# schematic.net
KiCad netlist of a schematic drawn in EAGLE
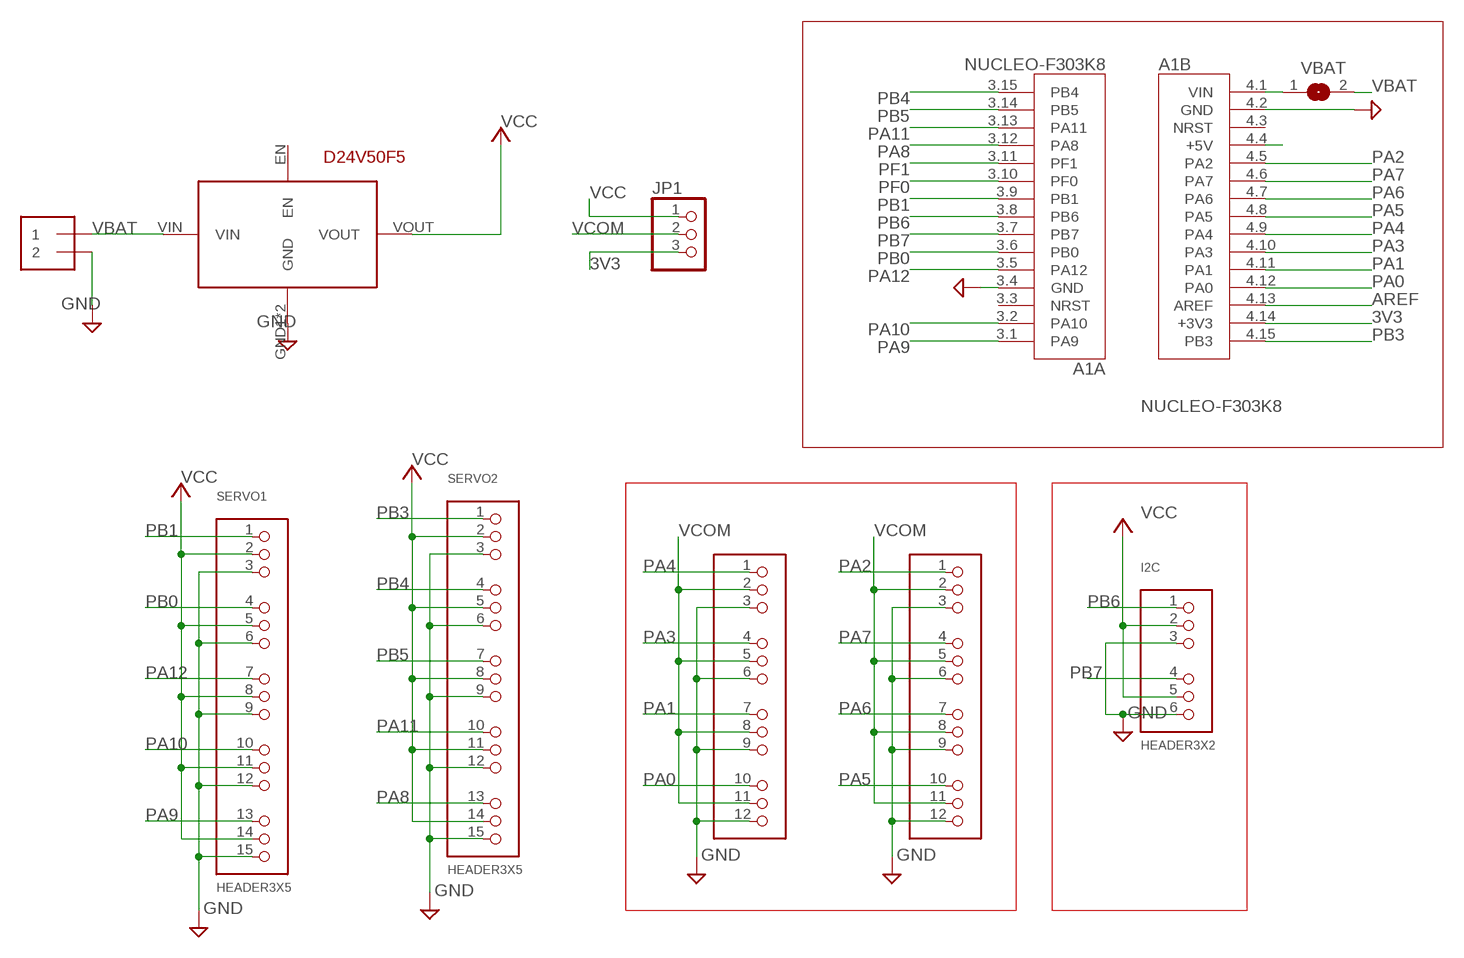
[diagram p0: schematic, sheet 1]

(export (version "E")
  (design (tool "Eeschema 10.0.6"))
  (components
    (comp (ref "A1")
      (value "NUCLEO-F303K8")
      (footprint "eagle-import:MODULE_NUCLEO-F303K8")
      (fields (field (name "MF") "STMicroelectronics"))
      (libsource (lib "eagle-import") (part "NUCLEO-F303K8"))
    )
    (comp (ref "ADC")
      (value "HEADER-3X04")
      (footprint "eagle-import:3X04")
      (fields (field (name "SPICEPREFIX") "X"))
      (libsource (lib "eagle-import") (part "HEADER-3X04"))
    )
    (comp (ref "ADC_DAC")
      (value "HEADER-3X04")
      (footprint "eagle-import:3X04")
      (libsource (lib "eagle-import") (part "HEADER-3X04"))
    )
    (comp (ref "I2C")
      (value "HEADER3X2")
      (footprint "eagle-import:HEADER3X2")
      (libsource (lib "eagle-import") (part "HEADER3X2"))
    )
    (comp (ref "J1")
      (value "1X2-3.5MM")
      (footprint "eagle-import:1X2-3.5MM")
      (libsource (lib "eagle-import") (part "1X2-3.5MM"))
    )
    (comp (ref "JP1")
      (value "PINHD-1X3")
      (footprint "eagle-import:1X03")
      (libsource (lib "eagle-import") (part "PINHD-1X3"))
    )
    (comp (ref "SERVO1")
      (value "HEADER3X5")
      (footprint "eagle-import:HEADER3X5")
      (libsource (lib "eagle-import") (part "HEADER3X5"))
    )
    (comp (ref "SERVO2")
      (value "HEADER3X5")
      (footprint "eagle-import:HEADER3X5")
      (libsource (lib "eagle-import") (part "HEADER3X5"))
    )
    (comp (ref "U$1")
      (value "D24V50F5")
      (footprint "eagle-import:D24V50F5")
      (libsource (lib "eagle-import") (part "D24V50F5"))
    )
    (comp (ref "VBAT")
      (value "SJW")
      (footprint "eagle-import:SJW")
      (libsource (lib "eagle-import") (part "SJW"))
    )
  )
  (nets
    (net (code "1") (name "/3V3") (class "Default")
      (node (ref "A1") (pin "4.14") (pinfunction "+3V3_4.14") (pintype "bidirectional"))
      (node (ref "JP1") (pin "3") (pinfunction "3_3") (pintype "passive"))
    )
    (net (code "2") (name "/AREF") (class "Default")
      (node (ref "A1") (pin "4.13") (pinfunction "AREF_4.13") (pintype "bidirectional"))
    )
    (net (code "3") (name "/PA0") (class "Default")
      (node (ref "A1") (pin "4.12") (pinfunction "PA0_4.12") (pintype "bidirectional"))
      (node (ref "ADC") (pin "10") (pinfunction "10_10") (pintype "passive"))
    )
    (net (code "4") (name "/PA1") (class "Default")
      (node (ref "A1") (pin "4.11") (pinfunction "PA1_4.11") (pintype "bidirectional"))
      (node (ref "ADC") (pin "7") (pinfunction "7_7") (pintype "passive"))
    )
    (net (code "5") (name "/PA2") (class "Default")
      (node (ref "A1") (pin "4.5") (pinfunction "PA2_4.5") (pintype "bidirectional"))
      (node (ref "ADC_DAC") (pin "1") (pinfunction "1_1") (pintype "passive"))
    )
    (net (code "6") (name "/PA3") (class "Default")
      (node (ref "A1") (pin "4.10") (pinfunction "PA3_4.10") (pintype "bidirectional"))
      (node (ref "ADC") (pin "4") (pinfunction "4_4") (pintype "passive"))
    )
    (net (code "7") (name "/PA4") (class "Default")
      (node (ref "A1") (pin "4.9") (pinfunction "PA4_4.9") (pintype "bidirectional"))
      (node (ref "ADC") (pin "1") (pinfunction "1_1") (pintype "passive"))
    )
    (net (code "8") (name "/PA5") (class "Default")
      (node (ref "A1") (pin "4.8") (pinfunction "PA5_4.8") (pintype "bidirectional"))
      (node (ref "ADC_DAC") (pin "10") (pinfunction "10_10") (pintype "passive"))
    )
    (net (code "9") (name "/PA6") (class "Default")
      (node (ref "A1") (pin "4.7") (pinfunction "PA6_4.7") (pintype "bidirectional"))
      (node (ref "ADC_DAC") (pin "7") (pinfunction "7_7") (pintype "passive"))
    )
    (net (code "10") (name "/PA7") (class "Default")
      (node (ref "A1") (pin "4.6") (pinfunction "PA7_4.6") (pintype "bidirectional"))
      (node (ref "ADC_DAC") (pin "4") (pinfunction "4_4") (pintype "passive"))
    )
    (net (code "11") (name "/PA8") (class "Default")
      (node (ref "A1") (pin "3.12") (pinfunction "PA8_3.12") (pintype "bidirectional"))
      (node (ref "SERVO2") (pin "13") (pinfunction "13_13") (pintype "passive"))
    )
    (net (code "12") (name "/PA9") (class "Default")
      (node (ref "A1") (pin "3.1") (pinfunction "PA9_3.1") (pintype "bidirectional"))
      (node (ref "SERVO1") (pin "13") (pinfunction "13_13") (pintype "passive"))
    )
    (net (code "13") (name "/PA10") (class "Default")
      (node (ref "A1") (pin "3.2") (pinfunction "PA10_3.2") (pintype "bidirectional"))
      (node (ref "SERVO1") (pin "10") (pinfunction "10_10") (pintype "passive"))
    )
    (net (code "14") (name "/PA11") (class "Default")
      (node (ref "A1") (pin "3.13") (pinfunction "PA11_3.13") (pintype "bidirectional"))
      (node (ref "SERVO2") (pin "10") (pinfunction "10_10") (pintype "passive"))
    )
    (net (code "15") (name "/PA12") (class "Default")
      (node (ref "A1") (pin "3.5") (pinfunction "PA12_3.5") (pintype "bidirectional"))
      (node (ref "SERVO1") (pin "7") (pinfunction "7_7") (pintype "passive"))
    )
    (net (code "16") (name "/PB0") (class "Default")
      (node (ref "A1") (pin "3.6") (pinfunction "PB0_3.6") (pintype "bidirectional"))
      (node (ref "SERVO1") (pin "4") (pinfunction "4_4") (pintype "passive"))
    )
    (net (code "17") (name "/PB1") (class "Default")
      (node (ref "A1") (pin "3.9") (pinfunction "PB1_3.9") (pintype "bidirectional"))
      (node (ref "SERVO1") (pin "1") (pinfunction "1_1") (pintype "passive"))
    )
    (net (code "18") (name "/PB3") (class "Default")
      (node (ref "A1") (pin "4.15") (pinfunction "PB3_4.15") (pintype "bidirectional"))
      (node (ref "SERVO2") (pin "1") (pinfunction "1_1") (pintype "passive"))
    )
    (net (code "19") (name "/PB4") (class "Default")
      (node (ref "A1") (pin "3.15") (pinfunction "PB4_3.15") (pintype "bidirectional"))
      (node (ref "SERVO2") (pin "4") (pinfunction "4_4") (pintype "passive"))
    )
    (net (code "20") (name "/PB5") (class "Default")
      (node (ref "A1") (pin "3.14") (pinfunction "PB5_3.14") (pintype "bidirectional"))
      (node (ref "SERVO2") (pin "7") (pinfunction "7_7") (pintype "passive"))
    )
    (net (code "21") (name "/PB6") (class "Default")
      (node (ref "A1") (pin "3.8") (pinfunction "PB6_3.8") (pintype "bidirectional"))
      (node (ref "I2C") (pin "1") (pinfunction "1_1") (pintype "passive"))
    )
    (net (code "22") (name "/PB7") (class "Default")
      (node (ref "A1") (pin "3.7") (pinfunction "PB7_3.7") (pintype "bidirectional"))
      (node (ref "I2C") (pin "4") (pinfunction "4_4") (pintype "passive"))
    )
    (net (code "23") (name "/PF0") (class "Default")
      (node (ref "A1") (pin "3.10") (pinfunction "PF0_3.10") (pintype "bidirectional"))
    )
    (net (code "24") (name "/PF1") (class "Default")
      (node (ref "A1") (pin "3.11") (pinfunction "PF1_3.11") (pintype "bidirectional"))
    )
    (net (code "25") (name "/VBAT") (class "Default")
      (node (ref "J1") (pin "1") (pinfunction "1_1") (pintype "passive"))
      (node (ref "U$1") (pin "VIN") (pinfunction "VIN_VIN") (pintype "bidirectional"))
      (node (ref "VBAT") (pin "2") (pinfunction "2_2") (pintype "passive"))
    )
    (net (code "26") (name "/VCOM") (class "Default")
      (node (ref "ADC") (pin "11") (pinfunction "11_11") (pintype "passive"))
      (node (ref "ADC") (pin "2") (pinfunction "2_2") (pintype "passive"))
      (node (ref "ADC") (pin "5") (pinfunction "5_5") (pintype "passive"))
      (node (ref "ADC") (pin "8") (pinfunction "8_8") (pintype "passive"))
      (node (ref "ADC_DAC") (pin "11") (pinfunction "11_11") (pintype "passive"))
      (node (ref "ADC_DAC") (pin "2") (pinfunction "2_2") (pintype "passive"))
      (node (ref "ADC_DAC") (pin "5") (pinfunction "5_5") (pintype "passive"))
      (node (ref "ADC_DAC") (pin "8") (pinfunction "8_8") (pintype "passive"))
      (node (ref "JP1") (pin "2") (pinfunction "2_2") (pintype "passive"))
    )
    (net (code "27") (name "GND") (class "Default")
      (node (ref "A1") (pin "3.4") (pinfunction "GND_3.4") (pintype "bidirectional"))
      (node (ref "A1") (pin "4.2") (pinfunction "GND_4.2") (pintype "bidirectional"))
      (node (ref "ADC") (pin "12") (pinfunction "12_12") (pintype "passive"))
      (node (ref "ADC") (pin "3") (pinfunction "3_3") (pintype "passive"))
      (node (ref "ADC") (pin "6") (pinfunction "6_6") (pintype "passive"))
      (node (ref "ADC") (pin "9") (pinfunction "9_9") (pintype "passive"))
      (node (ref "ADC_DAC") (pin "12") (pinfunction "12_12") (pintype "passive"))
      (node (ref "ADC_DAC") (pin "3") (pinfunction "3_3") (pintype "passive"))
      (node (ref "ADC_DAC") (pin "6") (pinfunction "6_6") (pintype "passive"))
      (node (ref "ADC_DAC") (pin "9") (pinfunction "9_9") (pintype "passive"))
      (node (ref "I2C") (pin "3") (pinfunction "3_3") (pintype "passive"))
      (node (ref "I2C") (pin "6") (pinfunction "6_6") (pintype "passive"))
      (node (ref "J1") (pin "2") (pinfunction "2_2") (pintype "passive"))
      (node (ref "SERVO1") (pin "12") (pinfunction "12_12") (pintype "passive"))
      (node (ref "SERVO1") (pin "15") (pinfunction "15_15") (pintype "passive"))
      (node (ref "SERVO1") (pin "3") (pinfunction "3_3") (pintype "passive"))
      (node (ref "SERVO1") (pin "6") (pinfunction "6_6") (pintype "passive"))
      (node (ref "SERVO1") (pin "9") (pinfunction "9_9") (pintype "passive"))
      (node (ref "SERVO2") (pin "12") (pinfunction "12_12") (pintype "passive"))
      (node (ref "SERVO2") (pin "15") (pinfunction "15_15") (pintype "passive"))
      (node (ref "SERVO2") (pin "3") (pinfunction "3_3") (pintype "passive"))
      (node (ref "SERVO2") (pin "6") (pinfunction "6_6") (pintype "passive"))
      (node (ref "SERVO2") (pin "9") (pinfunction "9_9") (pintype "passive"))
      (node (ref "U$1") (pin "GND1") (pinfunction "GND_GND1") (pintype "bidirectional"))
      (node (ref "U$1") (pin "GND2") (pinfunction "GND_GND2") (pintype "bidirectional"))
    )
    (net (code "28") (name "Net-(A1B-VIN)") (class "Default")
      (node (ref "A1") (pin "4.1") (pinfunction "VIN_4.1") (pintype "bidirectional"))
      (node (ref "VBAT") (pin "1") (pinfunction "1_1") (pintype "passive"))
    )
    (net (code "29") (name "VCC") (class "Default")
      (node (ref "I2C") (pin "2") (pinfunction "2_2") (pintype "passive"))
      (node (ref "I2C") (pin "5") (pinfunction "5_5") (pintype "passive"))
      (node (ref "JP1") (pin "1") (pinfunction "1_1") (pintype "passive"))
      (node (ref "SERVO1") (pin "11") (pinfunction "11_11") (pintype "passive"))
      (node (ref "SERVO1") (pin "14") (pinfunction "14_14") (pintype "passive"))
      (node (ref "SERVO1") (pin "2") (pinfunction "2_2") (pintype "passive"))
      (node (ref "SERVO1") (pin "5") (pinfunction "5_5") (pintype "passive"))
      (node (ref "SERVO1") (pin "8") (pinfunction "8_8") (pintype "passive"))
      (node (ref "SERVO2") (pin "11") (pinfunction "11_11") (pintype "passive"))
      (node (ref "SERVO2") (pin "14") (pinfunction "14_14") (pintype "passive"))
      (node (ref "SERVO2") (pin "2") (pinfunction "2_2") (pintype "passive"))
      (node (ref "SERVO2") (pin "5") (pinfunction "5_5") (pintype "passive"))
      (node (ref "SERVO2") (pin "8") (pinfunction "8_8") (pintype "passive"))
      (node (ref "U$1") (pin "VOUT") (pinfunction "VOUT_VOUT") (pintype "bidirectional"))
    )
    (net (code "30") (name "unconnected-(A1A-NRST-Pad3.3)") (class "Default")
      (node (ref "A1") (pin "3.3") (pinfunction "NRST_3.3") (pintype "bidirectional"))
    )
    (net (code "31") (name "unconnected-(A1B-+5V-Pad4.4)") (class "Default")
      (node (ref "A1") (pin "4.4") (pinfunction "+5V_4.4") (pintype "bidirectional"))
    )
    (net (code "32") (name "unconnected-(A1B-NRST-Pad4.3)") (class "Default")
      (node (ref "A1") (pin "4.3") (pinfunction "NRST_4.3") (pintype "bidirectional"))
    )
    (net (code "33") (name "unconnected-(U$1-PadEN)") (class "Default")
      (node (ref "U$1") (pin "EN") (pinfunction "EN_EN") (pintype "bidirectional"))
    )
  )
)
